# TopAndBotShieldV2-4.net
KiCad netlist of a schematic drawn in EAGLE
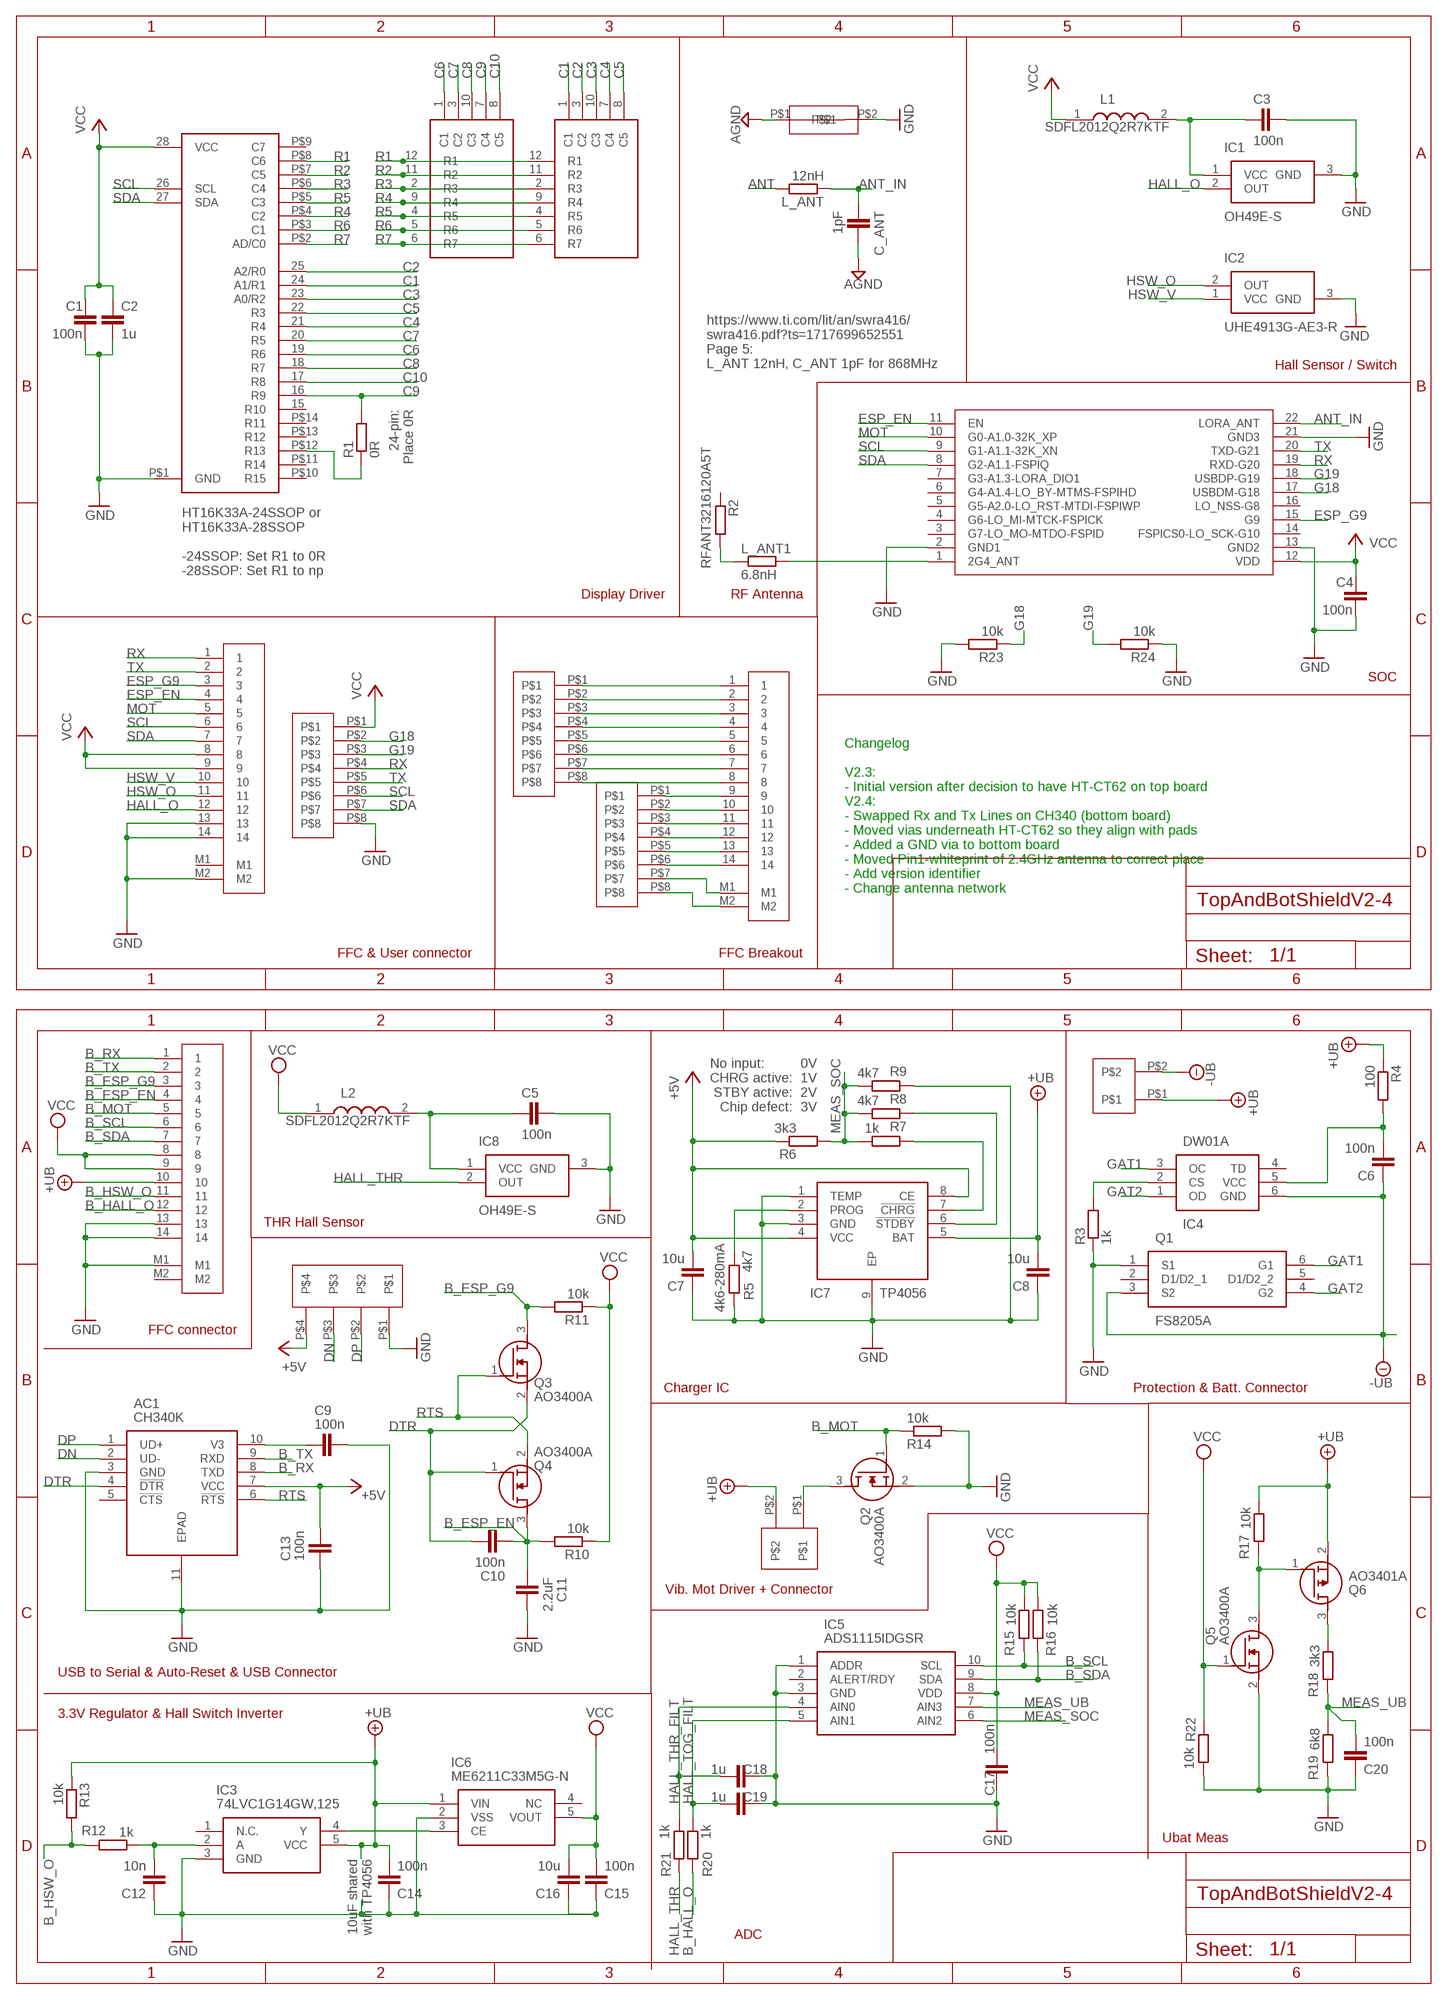
[diagram p0: schematic, sheet 1]

(export (version "E")
  (design (tool "Eeschema 10.0.6"))
  (components
    (comp (ref "AC1")
      (value "CH340K")
      (footprint "eagle-import:SOP100P600X180-11N")
      (libsource (lib "eagle-import") (part "CH340K"))
    )
    (comp (ref "C1")
      (value "100n")
      (footprint "eagle-import:C0603")
      (libsource (lib "eagle-import") (part "C-EUC0603"))
    )
    (comp (ref "C2")
      (value "1u")
      (footprint "eagle-import:C0603")
      (libsource (lib "eagle-import") (part "C-EUC0603"))
    )
    (comp (ref "C3")
      (value "100n")
      (footprint "eagle-import:C0603")
      (libsource (lib "eagle-import") (part "C-EUC0603"))
    )
    (comp (ref "C4")
      (value "100n")
      (footprint "eagle-import:C0603")
      (libsource (lib "eagle-import") (part "C-EUC0603"))
    )
    (comp (ref "C5")
      (value "100n")
      (footprint "eagle-import:C0603")
      (libsource (lib "eagle-import") (part "C-EUC0603"))
    )
    (comp (ref "C6")
      (value "100n")
      (footprint "eagle-import:C0603")
      (libsource (lib "eagle-import") (part "C-EUC0603"))
    )
    (comp (ref "C7")
      (value "10u")
      (footprint "eagle-import:C0603")
      (libsource (lib "eagle-import") (part "C-EUC0603"))
    )
    (comp (ref "C8")
      (value "10u")
      (footprint "eagle-import:C0603")
      (libsource (lib "eagle-import") (part "C-EUC0603"))
    )
    (comp (ref "C9")
      (value "100n")
      (footprint "eagle-import:C0603")
      (libsource (lib "eagle-import") (part "C-EUC0603"))
    )
    (comp (ref "C10")
      (value "100n")
      (footprint "eagle-import:C0603")
      (libsource (lib "eagle-import") (part "C-EUC0603"))
    )
    (comp (ref "C11")
      (value "2.2uF")
      (footprint "eagle-import:C0603")
      (libsource (lib "eagle-import") (part "C-EUC0603"))
    )
    (comp (ref "C12")
      (value "10n")
      (footprint "eagle-import:C0603")
      (libsource (lib "eagle-import") (part "C-EUC0603"))
    )
    (comp (ref "C13")
      (value "100n")
      (footprint "eagle-import:C0603")
      (libsource (lib "eagle-import") (part "C-EUC0603"))
    )
    (comp (ref "C14")
      (value "100n")
      (footprint "eagle-import:C0603")
      (libsource (lib "eagle-import") (part "C-EUC0603"))
    )
    (comp (ref "C15")
      (value "100n")
      (footprint "eagle-import:C0603")
      (libsource (lib "eagle-import") (part "C-EUC0603"))
    )
    (comp (ref "C16")
      (value "10u")
      (footprint "eagle-import:C0603")
      (libsource (lib "eagle-import") (part "C-EUC0603"))
    )
    (comp (ref "C17")
      (value "100n")
      (footprint "eagle-import:C0603")
      (libsource (lib "eagle-import") (part "C-EUC0603"))
    )
    (comp (ref "C18")
      (value "1u")
      (footprint "eagle-import:C0603")
      (libsource (lib "eagle-import") (part "C-EUC0603"))
    )
    (comp (ref "C19")
      (value "1u")
      (footprint "eagle-import:C0603")
      (libsource (lib "eagle-import") (part "C-EUC0603"))
    )
    (comp (ref "C20")
      (value "100n")
      (footprint "eagle-import:C0603")
      (libsource (lib "eagle-import") (part "C-EUC0603"))
    )
    (comp (ref "C_ANT")
      (value "1pF")
      (footprint "eagle-import:C0402")
      (libsource (lib "eagle-import") (part "C-EUC0402"))
    )
    (comp (ref "IC1")
      (value "OH49E-S")
      (footprint "eagle-import:SOT95P237X112-3N")
      (fields
        (field (name "ARROW_PART_NUMBER") "DRV5055A3QDBZR")
        (field (name "MOUSER_PART_NUMBER") "595-DRV5055A3QDBZR")
      )
      (libsource (lib "eagle-import") (part "DRV5055A3QDBZR"))
    )
    (comp (ref "IC2")
      (value "UHE4913G-AE3-R")
      (footprint "eagle-import:SOT95P237X112-3N")
      (fields
        (field (name "ARROW_PART_NUMBER") "DRV5055A3QDBZR")
        (field (name "MOUSER_PART_NUMBER") "595-DRV5055A3QDBZR")
      )
      (libsource (lib "eagle-import") (part "DRV5055A3QDBZR"))
    )
    (comp (ref "IC3")
      (value "74LVC1G14GW,125")
      (footprint "eagle-import:SOT65P212X110-5N")
      (fields (field (name "MOUSER_PART_NUMBER") "771-74LVC1G14GW-G"))
      (libsource (lib "eagle-import") (part "74LVC1G14GW,125"))
    )
    (comp (ref "IC4")
      (value "DW01A")
      (footprint "eagle-import:SOT95P280X135-6N")
      (fields (field (name "MANUFACTURER_PART_NUMBER") "DW01A-G"))
      (libsource (lib "eagle-import") (part "DW01A-G"))
    )
    (comp (ref "IC5")
      (value "ADS1115IDGSR")
      (footprint "eagle-import:SOP50P490X110-10N")
      (fields (field (name "MOUSER_PART_NUMBER") "595-ADS1115IDGSR"))
      (libsource (lib "eagle-import") (part "ADS1115IDGSR"))
    )
    (comp (ref "IC6")
      (value "ME6211C33M5G-N")
      (footprint "eagle-import:SOT95P282X145-5N")
      (fields (field (name "MANUFACTURER_PART_NUMBER") "ME6211C50M5G"))
      (libsource (lib "eagle-import") (part "ME6211C50M5G"))
    )
    (comp (ref "IC7")
      (value "TP4056")
      (footprint "eagle-import:SOIC127P600X175-9N")
      (fields (field (name "MANUFACTURER_PART_NUMBER") "TP4056-42-ESOP8"))
      (libsource (lib "eagle-import") (part "TP4056-42-ESOP8"))
    )
    (comp (ref "IC8")
      (value "OH49E-S")
      (footprint "eagle-import:SOT95P237X112-3N")
      (fields
        (field (name "ARROW_PART_NUMBER") "DRV5055A3QDBZR")
        (field (name "MOUSER_PART_NUMBER") "595-DRV5055A3QDBZR")
      )
      (libsource (lib "eagle-import") (part "DRV5055A3QDBZR"))
    )
    (comp (ref "L1")
      (value "SDFL2012Q2R7KTF")
      (footprint "eagle-import:INDC2112X105N")
      (libsource (lib "eagle-import") (part "SDFL2012Q2R7KTF"))
    )
    (comp (ref "L2")
      (value "SDFL2012Q2R7KTF")
      (footprint "eagle-import:INDC2112X105N")
      (libsource (lib "eagle-import") (part "SDFL2012Q2R7KTF"))
    )
    (comp (ref "L_ANT")
      (value "12nH")
      (footprint "eagle-import:R0402")
      (libsource (lib "eagle-import") (part "R-EU_R0402"))
    )
    (comp (ref "L_ANT1")
      (value "6.8nH")
      (footprint "eagle-import:R0402")
      (libsource (lib "eagle-import") (part "R-EU_R0402"))
    )
    (comp (ref "Q1")
      (value "FS8205A")
      (footprint "eagle-import:SOT95P280X125-6N")
      (libsource (lib "eagle-import") (part "FS8205A"))
    )
    (comp (ref "Q2")
      (value "AO3400A")
      (footprint "eagle-import:SOT95P280X125-3N")
      (libsource (lib "eagle-import") (part "AO3400A"))
    )
    (comp (ref "Q3")
      (value "AO3400A")
      (footprint "eagle-import:SOT95P280X125-3N")
      (libsource (lib "eagle-import") (part "AO3400A"))
    )
    (comp (ref "Q4")
      (value "AO3400A")
      (footprint "eagle-import:SOT95P280X125-3N")
      (libsource (lib "eagle-import") (part "AO3400A"))
    )
    (comp (ref "Q5")
      (value "AO3400A")
      (footprint "eagle-import:SOT95P280X125-3N")
      (libsource (lib "eagle-import") (part "AO3400A"))
    )
    (comp (ref "Q6")
      (value "AO3401A")
      (footprint "eagle-import:SOT95P280X125-3N")
      (libsource (lib "eagle-import") (part "AO3401A"))
    )
    (comp (ref "R1")
      (value "0R")
      (footprint "eagle-import:R0603")
      (libsource (lib "eagle-import") (part "R-EU_R0603"))
    )
    (comp (ref "R2")
      (value "RFANT3216120A5T")
      (footprint "eagle-import:R1206")
      (libsource (lib "eagle-import") (part "R-EU_R1206"))
    )
    (comp (ref "R3")
      (value "1k")
      (footprint "eagle-import:R0603")
      (libsource (lib "eagle-import") (part "R-EU_R0603"))
    )
    (comp (ref "R4")
      (value "100")
      (footprint "eagle-import:R0603")
      (libsource (lib "eagle-import") (part "R-EU_R0603"))
    )
    (comp (ref "R5")
      (value "4k7")
      (footprint "eagle-import:R0603")
      (libsource (lib "eagle-import") (part "R-EU_R0603"))
    )
    (comp (ref "R6")
      (value "3k3")
      (footprint "eagle-import:R0603")
      (libsource (lib "eagle-import") (part "R-EU_R0603"))
    )
    (comp (ref "R7")
      (value "1k")
      (footprint "eagle-import:R0603")
      (libsource (lib "eagle-import") (part "R-EU_R0603"))
    )
    (comp (ref "R8")
      (value "4k7")
      (footprint "eagle-import:R0603")
      (libsource (lib "eagle-import") (part "R-EU_R0603"))
    )
    (comp (ref "R9")
      (value "4k7")
      (footprint "eagle-import:R0603")
      (libsource (lib "eagle-import") (part "R-EU_R0603"))
    )
    (comp (ref "R10")
      (value "10k")
      (footprint "eagle-import:R0603")
      (libsource (lib "eagle-import") (part "R-EU_R0603"))
    )
    (comp (ref "R11")
      (value "10k")
      (footprint "eagle-import:R0603")
      (libsource (lib "eagle-import") (part "R-EU_R0603"))
    )
    (comp (ref "R12")
      (value "1k")
      (footprint "eagle-import:R0603")
      (libsource (lib "eagle-import") (part "R-EU_R0603"))
    )
    (comp (ref "R13")
      (value "10k")
      (footprint "eagle-import:R0603")
      (libsource (lib "eagle-import") (part "R-EU_R0603"))
    )
    (comp (ref "R14")
      (value "10k")
      (footprint "eagle-import:R0603")
      (libsource (lib "eagle-import") (part "R-EU_R0603"))
    )
    (comp (ref "R15")
      (value "10k")
      (footprint "eagle-import:R0603")
      (libsource (lib "eagle-import") (part "R-EU_R0603"))
    )
    (comp (ref "R16")
      (value "10k")
      (footprint "eagle-import:R0603")
      (libsource (lib "eagle-import") (part "R-EU_R0603"))
    )
    (comp (ref "R17")
      (value "10k")
      (footprint "eagle-import:R0603")
      (libsource (lib "eagle-import") (part "R-EU_R0603"))
    )
    (comp (ref "R18")
      (value "3k3")
      (footprint "eagle-import:R0603")
      (libsource (lib "eagle-import") (part "R-EU_R0603"))
    )
    (comp (ref "R19")
      (value "6k8")
      (footprint "eagle-import:R0603")
      (libsource (lib "eagle-import") (part "R-EU_R0603"))
    )
    (comp (ref "R20")
      (value "1k")
      (footprint "eagle-import:R0603")
      (libsource (lib "eagle-import") (part "R-EU_R0603"))
    )
    (comp (ref "R21")
      (value "1k")
      (footprint "eagle-import:R0603")
      (libsource (lib "eagle-import") (part "R-EU_R0603"))
    )
    (comp (ref "R22")
      (value "10k")
      (footprint "eagle-import:R0603")
      (libsource (lib "eagle-import") (part "R-EU_R0603"))
    )
    (comp (ref "R23")
      (value "10k")
      (footprint "eagle-import:R0603")
      (libsource (lib "eagle-import") (part "R-EU_R0603"))
    )
    (comp (ref "R24")
      (value "10k")
      (footprint "eagle-import:R0603")
      (libsource (lib "eagle-import") (part "R-EU_R0603"))
    )
    (comp (ref "U$1")
      (value "HT16K33A-24SSOP")
      (footprint "eagle-import:SSOP28")
      (libsource (lib "eagle-import") (part "HT16K33A"))
    )
    (comp (ref "U$2")
      (value "757A")
      (footprint "eagle-import:757A")
      (libsource (lib "eagle-import") (part "757A"))
    )
    (comp (ref "U$3")
      (value "757A")
      (footprint "eagle-import:757A")
      (libsource (lib "eagle-import") (part "757A"))
    )
    (comp (ref "U$4")
      (value "FPC-05F-14PH15")
      (footprint "eagle-import:FPC-05F-14PH15")
      (libsource (lib "eagle-import") (part "FPC-05F-14PH15"))
    )
    (comp (ref "U$5")
      (value "HT-CT62")
      (footprint "eagle-import:HT-CT62")
      (libsource (lib "eagle-import") (part "HT-CT62"))
    )
    (comp (ref "U$6")
      (value "FPC-05F-14PH15")
      (footprint "eagle-import:FPC-05F-14PH15")
      (libsource (lib "eagle-import") (part "FPC-05F-14PH15"))
    )
    (comp (ref "U$7")
      (value "NETTIE_0.6MM")
      (footprint "eagle-import:0.6MM")
      (libsource (lib "eagle-import") (part "NETTIE_0.6MM"))
    )
    (comp (ref "U$8")
      (value "8P")
      (footprint "eagle-import:8PIN")
      (libsource (lib "eagle-import") (part "8P"))
    )
    (comp (ref "U$9")
      (value "8P")
      (footprint "eagle-import:8PIN")
      (libsource (lib "eagle-import") (part "8P"))
    )
    (comp (ref "U$10")
      (value "8P")
      (footprint "eagle-import:8PIN")
      (libsource (lib "eagle-import") (part "8P"))
    )
    (comp (ref "U$11")
      (value "FPC-05F-14PH15")
      (footprint "eagle-import:FPC-05F-14PH15")
      (libsource (lib "eagle-import") (part "FPC-05F-14PH15"))
    )
    (comp (ref "U$12")
      (value "2P")
      (footprint "eagle-import:2PAD")
      (libsource (lib "eagle-import") (part "2P"))
    )
    (comp (ref "U$13")
      (value "2P")
      (footprint "eagle-import:2PAD")
      (libsource (lib "eagle-import") (part "2P"))
    )
    (comp (ref "U$14")
      (value "4P")
      (footprint "eagle-import:4PAD")
      (libsource (lib "eagle-import") (part "4P"))
    )
  )
  (nets
    (net (code "1") (name "+5V") (class "Default")
      (node (ref "AC1") (pin "7") (pinfunction "VCC_7") (pintype "power_in"))
      (node (ref "C13") (pin "1") (pinfunction "1_1") (pintype "passive"))
      (node (ref "C7") (pin "2") (pinfunction "2_2") (pintype "passive"))
      (node (ref "IC7") (pin "4") (pinfunction "VCC_4") (pintype "bidirectional"))
      (node (ref "IC7") (pin "8") (pinfunction "CE_8") (pintype "bidirectional"))
      (node (ref "R6") (pin "2") (pinfunction "2_2") (pintype "passive"))
      (node (ref "U$14") (pin "P$4") (pinfunction "P$4_P$4") (pintype "bidirectional"))
    )
    (net (code "2") (name "+UB") (class "Default")
      (node (ref "C14") (pin "2") (pinfunction "2_2") (pintype "passive"))
      (node (ref "C8") (pin "2") (pinfunction "2_2") (pintype "passive"))
      (node (ref "IC3") (pin "5") (pinfunction "VCC_5") (pintype "bidirectional"))
      (node (ref "IC6") (pin "1") (pinfunction "VIN_1") (pintype "bidirectional"))
      (node (ref "IC7") (pin "5") (pinfunction "BAT_5") (pintype "bidirectional"))
      (node (ref "Q6") (pin "2") (pinfunction "S_2") (pintype "bidirectional"))
      (node (ref "R13") (pin "1") (pinfunction "1_1") (pintype "passive"))
      (node (ref "R17") (pin "1") (pinfunction "1_1") (pintype "passive"))
      (node (ref "R4") (pin "1") (pinfunction "1_1") (pintype "passive"))
      (node (ref "U$11") (pin "10") (pinfunction "10_10") (pintype "bidirectional"))
      (node (ref "U$12") (pin "P$1") (pinfunction "P$1_P$1") (pintype "bidirectional"))
      (node (ref "U$13") (pin "P$2") (pinfunction "P$2_P$2") (pintype "bidirectional"))
    )
    (net (code "3") (name "-UB") (class "Default")
      (node (ref "C6") (pin "1") (pinfunction "1_1") (pintype "passive"))
      (node (ref "IC4") (pin "6") (pinfunction "GND_6") (pintype "bidirectional"))
      (node (ref "Q1") (pin "3") (pinfunction "S2_3") (pintype "bidirectional"))
      (node (ref "U$12") (pin "P$2") (pinfunction "P$2_P$2") (pintype "bidirectional"))
    )
    (net (code "4") (name "/ANT") (class "Default")
      (node (ref "L_ANT") (pin "2") (pinfunction "2_2") (pintype "passive"))
    )
    (net (code "5") (name "/ANT_IN") (class "Default")
      (node (ref "C_ANT") (pin "1") (pinfunction "1_1") (pintype "passive"))
      (node (ref "L_ANT") (pin "1") (pinfunction "1_1") (pintype "passive"))
      (node (ref "U$5") (pin "22") (pinfunction "LORA_ANT_22") (pintype "bidirectional"))
    )
    (net (code "6") (name "/B_ESP_EN") (class "Default")
      (node (ref "C10") (pin "2") (pinfunction "2_2") (pintype "passive"))
      (node (ref "C11") (pin "2") (pinfunction "2_2") (pintype "passive"))
      (node (ref "Q4") (pin "3") (pinfunction "D_3") (pintype "bidirectional"))
      (node (ref "R10") (pin "2") (pinfunction "2_2") (pintype "passive"))
      (node (ref "U$11") (pin "4") (pinfunction "4_4") (pintype "bidirectional"))
    )
    (net (code "7") (name "/B_ESP_G9") (class "Default")
      (node (ref "Q3") (pin "3") (pinfunction "D_3") (pintype "bidirectional"))
      (node (ref "R11") (pin "2") (pinfunction "2_2") (pintype "passive"))
      (node (ref "U$11") (pin "3") (pinfunction "3_3") (pintype "bidirectional"))
    )
    (net (code "8") (name "/B_HALL_O") (class "Default")
      (node (ref "R20") (pin "2") (pinfunction "2_2") (pintype "passive"))
      (node (ref "U$11") (pin "12") (pinfunction "12_12") (pintype "bidirectional"))
    )
    (net (code "9") (name "/B_HSW_O") (class "Default")
      (node (ref "R12") (pin "2") (pinfunction "2_2") (pintype "passive"))
      (node (ref "R13") (pin "2") (pinfunction "2_2") (pintype "passive"))
      (node (ref "U$11") (pin "11") (pinfunction "11_11") (pintype "bidirectional"))
    )
    (net (code "10") (name "/B_MOT") (class "Default")
      (node (ref "Q2") (pin "1") (pinfunction "G_1") (pintype "bidirectional"))
      (node (ref "R14") (pin "1") (pinfunction "1_1") (pintype "passive"))
      (node (ref "U$11") (pin "5") (pinfunction "5_5") (pintype "bidirectional"))
    )
    (net (code "11") (name "/B_RX") (class "Default")
      (node (ref "AC1") (pin "8") (pinfunction "TXD_8") (pintype "bidirectional"))
      (node (ref "U$11") (pin "1") (pinfunction "1_1") (pintype "bidirectional"))
    )
    (net (code "12") (name "/B_SCL") (class "Default")
      (node (ref "IC5") (pin "10") (pinfunction "SCL_10") (pintype "bidirectional"))
      (node (ref "R15") (pin "2") (pinfunction "2_2") (pintype "passive"))
      (node (ref "U$11") (pin "6") (pinfunction "6_6") (pintype "bidirectional"))
    )
    (net (code "13") (name "/B_SDA") (class "Default")
      (node (ref "IC5") (pin "9") (pinfunction "SDA_9") (pintype "bidirectional"))
      (node (ref "R16") (pin "2") (pinfunction "2_2") (pintype "passive"))
      (node (ref "U$11") (pin "7") (pinfunction "7_7") (pintype "bidirectional"))
    )
    (net (code "14") (name "/B_TX") (class "Default")
      (node (ref "AC1") (pin "9") (pinfunction "RXD_9") (pintype "bidirectional"))
      (node (ref "U$11") (pin "2") (pinfunction "2_2") (pintype "bidirectional"))
    )
    (net (code "15") (name "/C1") (class "Default")
      (node (ref "U$1") (pin "24") (pinfunction "A1/R1_24") (pintype "bidirectional"))
      (node (ref "U$3") (pin "1") (pinfunction "C1_1") (pintype "bidirectional"))
    )
    (net (code "16") (name "/C2") (class "Default")
      (node (ref "U$1") (pin "25") (pinfunction "A2/R0_25") (pintype "bidirectional"))
      (node (ref "U$3") (pin "3") (pinfunction "C2_3") (pintype "bidirectional"))
    )
    (net (code "17") (name "/C3") (class "Default")
      (node (ref "U$1") (pin "23") (pinfunction "A0/R2_23") (pintype "bidirectional"))
      (node (ref "U$3") (pin "10") (pinfunction "C3_10") (pintype "bidirectional"))
    )
    (net (code "18") (name "/C4") (class "Default")
      (node (ref "U$1") (pin "21") (pinfunction "R4_21") (pintype "bidirectional"))
      (node (ref "U$3") (pin "7") (pinfunction "C4_7") (pintype "bidirectional"))
    )
    (net (code "19") (name "/C5") (class "Default")
      (node (ref "U$1") (pin "22") (pinfunction "R3_22") (pintype "bidirectional"))
      (node (ref "U$3") (pin "8") (pinfunction "C5_8") (pintype "bidirectional"))
    )
    (net (code "20") (name "/C6") (class "Default")
      (node (ref "U$1") (pin "19") (pinfunction "R6_19") (pintype "bidirectional"))
      (node (ref "U$2") (pin "1") (pinfunction "C1_1") (pintype "bidirectional"))
    )
    (net (code "21") (name "/C7") (class "Default")
      (node (ref "U$1") (pin "20") (pinfunction "R5_20") (pintype "bidirectional"))
      (node (ref "U$2") (pin "3") (pinfunction "C2_3") (pintype "bidirectional"))
    )
    (net (code "22") (name "/C8") (class "Default")
      (node (ref "U$1") (pin "18") (pinfunction "R7_18") (pintype "bidirectional"))
      (node (ref "U$2") (pin "10") (pinfunction "C3_10") (pintype "bidirectional"))
    )
    (net (code "23") (name "/C9") (class "Default")
      (node (ref "R1") (pin "2") (pinfunction "2_2") (pintype "passive"))
      (node (ref "U$1") (pin "16") (pinfunction "R9_16") (pintype "bidirectional"))
      (node (ref "U$2") (pin "7") (pinfunction "C4_7") (pintype "bidirectional"))
    )
    (net (code "24") (name "/C10") (class "Default")
      (node (ref "U$1") (pin "17") (pinfunction "R8_17") (pintype "bidirectional"))
      (node (ref "U$2") (pin "8") (pinfunction "C5_8") (pintype "bidirectional"))
    )
    (net (code "25") (name "/DN") (class "Default")
      (node (ref "AC1") (pin "2") (pinfunction "UD-_2") (pintype "bidirectional"))
      (node (ref "U$14") (pin "P$3") (pinfunction "P$3_P$3") (pintype "bidirectional"))
    )
    (net (code "26") (name "/DP") (class "Default")
      (node (ref "AC1") (pin "1") (pinfunction "UD+_1") (pintype "bidirectional"))
      (node (ref "U$14") (pin "P$2") (pinfunction "P$2_P$2") (pintype "bidirectional"))
    )
    (net (code "27") (name "/DTR") (class "Default")
      (node (ref "AC1") (pin "4") (pinfunction "~{DTR}_4") (pintype "bidirectional"))
      (node (ref "C10") (pin "1") (pinfunction "1_1") (pintype "passive"))
      (node (ref "Q3") (pin "2") (pinfunction "S_2") (pintype "bidirectional"))
      (node (ref "Q4") (pin "1") (pinfunction "G_1") (pintype "bidirectional"))
    )
    (net (code "28") (name "/ESP_EN") (class "Default")
      (node (ref "U$5") (pin "11") (pinfunction "EN_11") (pintype "bidirectional"))
      (node (ref "U$6") (pin "4") (pinfunction "4_4") (pintype "bidirectional"))
    )
    (net (code "29") (name "/ESP_G9") (class "Default")
      (node (ref "U$5") (pin "15") (pinfunction "G9_15") (pintype "bidirectional"))
      (node (ref "U$6") (pin "3") (pinfunction "3_3") (pintype "bidirectional"))
    )
    (net (code "30") (name "/G18") (class "Default")
      (node (ref "R23") (pin "1") (pinfunction "1_1") (pintype "passive"))
      (node (ref "U$5") (pin "17") (pinfunction "USBDM-G18_17") (pintype "bidirectional"))
      (node (ref "U$8") (pin "P$2") (pinfunction "P$2_P$2") (pintype "bidirectional"))
    )
    (net (code "31") (name "/G19") (class "Default")
      (node (ref "R24") (pin "2") (pinfunction "2_2") (pintype "passive"))
      (node (ref "U$5") (pin "18") (pinfunction "USBDP-G19_18") (pintype "bidirectional"))
      (node (ref "U$8") (pin "P$3") (pinfunction "P$3_P$3") (pintype "bidirectional"))
    )
    (net (code "32") (name "/GAT1") (class "Default")
      (node (ref "IC4") (pin "3") (pinfunction "OC_3") (pintype "bidirectional"))
      (node (ref "Q1") (pin "6") (pinfunction "G1_6") (pintype "bidirectional"))
    )
    (net (code "33") (name "/GAT2") (class "Default")
      (node (ref "IC4") (pin "1") (pinfunction "OD_1") (pintype "bidirectional"))
      (node (ref "Q1") (pin "4") (pinfunction "G2_4") (pintype "bidirectional"))
    )
    (net (code "34") (name "/HALL_O") (class "Default")
      (node (ref "IC1") (pin "2") (pinfunction "OUT_2") (pintype "bidirectional"))
      (node (ref "U$6") (pin "12") (pinfunction "12_12") (pintype "bidirectional"))
    )
    (net (code "35") (name "/HALL_THR") (class "Default")
      (node (ref "IC8") (pin "2") (pinfunction "OUT_2") (pintype "bidirectional"))
      (node (ref "R21") (pin "2") (pinfunction "2_2") (pintype "passive"))
    )
    (net (code "36") (name "/HALL_THR_FILT") (class "Default")
      (node (ref "C18") (pin "1") (pinfunction "1_1") (pintype "passive"))
      (node (ref "IC5") (pin "4") (pinfunction "AIN0_4") (pintype "bidirectional"))
      (node (ref "R21") (pin "1") (pinfunction "1_1") (pintype "passive"))
    )
    (net (code "37") (name "/HALL_TOG_FILT") (class "Default")
      (node (ref "C19") (pin "1") (pinfunction "1_1") (pintype "passive"))
      (node (ref "IC5") (pin "5") (pinfunction "AIN1_5") (pintype "bidirectional"))
      (node (ref "R20") (pin "1") (pinfunction "1_1") (pintype "passive"))
    )
    (net (code "38") (name "/HSW_O") (class "Default")
      (node (ref "IC2") (pin "2") (pinfunction "OUT_2") (pintype "bidirectional"))
      (node (ref "U$6") (pin "11") (pinfunction "11_11") (pintype "bidirectional"))
    )
    (net (code "39") (name "/HSW_V") (class "Default")
      (node (ref "IC2") (pin "1") (pinfunction "VCC_1") (pintype "bidirectional"))
      (node (ref "U$6") (pin "10") (pinfunction "10_10") (pintype "bidirectional"))
    )
    (net (code "40") (name "/MEAS_SOC") (class "Default")
      (node (ref "IC5") (pin "6") (pinfunction "AIN2_6") (pintype "bidirectional"))
      (node (ref "R6") (pin "1") (pinfunction "1_1") (pintype "passive"))
      (node (ref "R7") (pin "2") (pinfunction "2_2") (pintype "passive"))
      (node (ref "R8") (pin "2") (pinfunction "2_2") (pintype "passive"))
      (node (ref "R9") (pin "2") (pinfunction "2_2") (pintype "passive"))
    )
    (net (code "41") (name "/MEAS_UB") (class "Default")
      (node (ref "C20") (pin "2") (pinfunction "2_2") (pintype "passive"))
      (node (ref "IC5") (pin "7") (pinfunction "AIN3_7") (pintype "bidirectional"))
      (node (ref "R18") (pin "2") (pinfunction "2_2") (pintype "passive"))
      (node (ref "R19") (pin "1") (pinfunction "1_1") (pintype "passive"))
    )
    (net (code "42") (name "/MOT") (class "Default")
      (node (ref "U$5") (pin "10") (pinfunction "G0-A1.0-32K_XP_10") (pintype "bidirectional"))
      (node (ref "U$6") (pin "5") (pinfunction "5_5") (pintype "bidirectional"))
    )
    (net (code "43") (name "/R1") (class "Default")
      (node (ref "U$1") (pin "P$8") (pinfunction "C6_P$8") (pintype "bidirectional"))
      (node (ref "U$2") (pin "12") (pinfunction "R1_12") (pintype "bidirectional"))
      (node (ref "U$3") (pin "12") (pinfunction "R1_12") (pintype "bidirectional"))
    )
    (net (code "44") (name "/R2") (class "Default")
      (node (ref "U$1") (pin "P$7") (pinfunction "C5_P$7") (pintype "bidirectional"))
      (node (ref "U$2") (pin "11") (pinfunction "R2_11") (pintype "bidirectional"))
      (node (ref "U$3") (pin "11") (pinfunction "R2_11") (pintype "bidirectional"))
    )
    (net (code "45") (name "/R3") (class "Default")
      (node (ref "U$1") (pin "P$6") (pinfunction "C4_P$6") (pintype "bidirectional"))
      (node (ref "U$2") (pin "2") (pinfunction "R3_2") (pintype "bidirectional"))
      (node (ref "U$3") (pin "2") (pinfunction "R3_2") (pintype "bidirectional"))
    )
    (net (code "46") (name "/R4") (class "Default")
      (node (ref "U$1") (pin "P$4") (pinfunction "C2_P$4") (pintype "bidirectional"))
      (node (ref "U$2") (pin "9") (pinfunction "R4_9") (pintype "bidirectional"))
      (node (ref "U$3") (pin "9") (pinfunction "R4_9") (pintype "bidirectional"))
    )
    (net (code "47") (name "/R5") (class "Default")
      (node (ref "U$1") (pin "P$5") (pinfunction "C3_P$5") (pintype "bidirectional"))
      (node (ref "U$2") (pin "4") (pinfunction "R5_4") (pintype "bidirectional"))
      (node (ref "U$3") (pin "4") (pinfunction "R5_4") (pintype "bidirectional"))
    )
    (net (code "48") (name "/R6") (class "Default")
      (node (ref "U$1") (pin "P$3") (pinfunction "C1_P$3") (pintype "bidirectional"))
      (node (ref "U$2") (pin "5") (pinfunction "R6_5") (pintype "bidirectional"))
      (node (ref "U$3") (pin "5") (pinfunction "R6_5") (pintype "bidirectional"))
    )
    (net (code "49") (name "/R7") (class "Default")
      (node (ref "U$1") (pin "P$2") (pinfunction "AD/C0_P$2") (pintype "bidirectional"))
      (node (ref "U$2") (pin "6") (pinfunction "R7_6") (pintype "bidirectional"))
      (node (ref "U$3") (pin "6") (pinfunction "R7_6") (pintype "bidirectional"))
    )
    (net (code "50") (name "/RTS") (class "Default")
      (node (ref "AC1") (pin "6") (pinfunction "~{RTS}_6") (pintype "bidirectional"))
      (node (ref "Q3") (pin "1") (pinfunction "G_1") (pintype "bidirectional"))
      (node (ref "Q4") (pin "2") (pinfunction "S_2") (pintype "bidirectional"))
    )
    (net (code "51") (name "/RX") (class "Default")
      (node (ref "U$5") (pin "19") (pinfunction "RXD-G20_19") (pintype "bidirectional"))
      (node (ref "U$6") (pin "1") (pinfunction "1_1") (pintype "bidirectional"))
      (node (ref "U$8") (pin "P$4") (pinfunction "P$4_P$4") (pintype "bidirectional"))
    )
    (net (code "52") (name "/SCL") (class "Default")
      (node (ref "U$1") (pin "26") (pinfunction "SCL_26") (pintype "bidirectional"))
      (node (ref "U$5") (pin "9") (pinfunction "G1-A1.1-32K_XN_9") (pintype "bidirectional"))
      (node (ref "U$6") (pin "6") (pinfunction "6_6") (pintype "bidirectional"))
      (node (ref "U$8") (pin "P$6") (pinfunction "P$6_P$6") (pintype "bidirectional"))
    )
    (net (code "53") (name "/SDA") (class "Default")
      (node (ref "U$1") (pin "27") (pinfunction "SDA_27") (pintype "bidirectional"))
      (node (ref "U$5") (pin "8") (pinfunction "G2-A1.1-FSPIQ_8") (pintype "bidirectional"))
      (node (ref "U$6") (pin "7") (pinfunction "7_7") (pintype "bidirectional"))
      (node (ref "U$8") (pin "P$7") (pinfunction "P$7_P$7") (pintype "bidirectional"))
    )
    (net (code "54") (name "/TX") (class "Default")
      (node (ref "U$5") (pin "20") (pinfunction "TXD-G21_20") (pintype "bidirectional"))
      (node (ref "U$6") (pin "2") (pinfunction "2_2") (pintype "bidirectional"))
      (node (ref "U$8") (pin "P$5") (pinfunction "P$5_P$5") (pintype "bidirectional"))
    )
    (net (code "55") (name "AGND") (class "Default")
      (node (ref "C_ANT") (pin "2") (pinfunction "2_2") (pintype "passive"))
      (node (ref "U$7") (pin "P$1") (pinfunction "P$1_P$1") (pintype "bidirectional"))
    )
    (net (code "56") (name "GND") (class "Default")
      (node (ref "AC1") (pin "11") (pinfunction "EPAD_11") (pintype "power_in"))
      (node (ref "AC1") (pin "3") (pinfunction "GND_3") (pintype "power_in"))
      (node (ref "C1") (pin "2") (pinfunction "2_2") (pintype "passive"))
      (node (ref "C11") (pin "1") (pinfunction "1_1") (pintype "passive"))
      (node (ref "C12") (pin "1") (pinfunction "1_1") (pintype "passive"))
      (node (ref "C13") (pin "2") (pinfunction "2_2") (pintype "passive"))
      (node (ref "C14") (pin "1") (pinfunction "1_1") (pintype "passive"))
      (node (ref "C15") (pin "1") (pinfunction "1_1") (pintype "passive"))
      (node (ref "C16") (pin "1") (pinfunction "1_1") (pintype "passive"))
      (node (ref "C17") (pin "2") (pinfunction "2_2") (pintype "passive"))
      (node (ref "C18") (pin "2") (pinfunction "2_2") (pintype "passive"))
      (node (ref "C19") (pin "2") (pinfunction "2_2") (pintype "passive"))
      (node (ref "C2") (pin "2") (pinfunction "2_2") (pintype "passive"))
      (node (ref "C20") (pin "1") (pinfunction "1_1") (pintype "passive"))
      (node (ref "C3") (pin "1") (pinfunction "1_1") (pintype "passive"))
      (node (ref "C4") (pin "2") (pinfunction "2_2") (pintype "passive"))
      (node (ref "C5") (pin "1") (pinfunction "1_1") (pintype "passive"))
      (node (ref "C7") (pin "1") (pinfunction "1_1") (pintype "passive"))
      (node (ref "C8") (pin "1") (pinfunction "1_1") (pintype "passive"))
      (node (ref "C9") (pin "1") (pinfunction "1_1") (pintype "passive"))
      (node (ref "IC1") (pin "3") (pinfunction "GND_3") (pintype "bidirectional"))
      (node (ref "IC2") (pin "3") (pinfunction "GND_3") (pintype "bidirectional"))
      (node (ref "IC3") (pin "3") (pinfunction "GND_3") (pintype "bidirectional"))
      (node (ref "IC5") (pin "1") (pinfunction "ADDR_1") (pintype "bidirectional"))
      (node (ref "IC5") (pin "3") (pinfunction "GND_3") (pintype "bidirectional"))
      (node (ref "IC6") (pin "2") (pinfunction "VSS_2") (pintype "bidirectional"))
      (node (ref "IC7") (pin "1") (pinfunction "TEMP_1") (pintype "bidirectional"))
      (node (ref "IC7") (pin "3") (pinfunction "GND_3") (pintype "bidirectional"))
      (node (ref "IC7") (pin "9") (pinfunction "EP_9") (pintype "bidirectional"))
      (node (ref "IC8") (pin "3") (pinfunction "GND_3") (pintype "bidirectional"))
      (node (ref "Q1") (pin "1") (pinfunction "S1_1") (pintype "bidirectional"))
      (node (ref "Q2") (pin "2") (pinfunction "S_2") (pintype "bidirectional"))
      (node (ref "Q5") (pin "2") (pinfunction "S_2") (pintype "bidirectional"))
      (node (ref "R14") (pin "2") (pinfunction "2_2") (pintype "passive"))
      (node (ref "R19") (pin "2") (pinfunction "2_2") (pintype "passive"))
      (node (ref "R22") (pin "1") (pinfunction "1_1") (pintype "passive"))
      (node (ref "R23") (pin "2") (pinfunction "2_2") (pintype "passive"))
      (node (ref "R24") (pin "1") (pinfunction "1_1") (pintype "passive"))
      (node (ref "R3") (pin "1") (pinfunction "1_1") (pintype "passive"))
      (node (ref "R5") (pin "1") (pinfunction "1_1") (pintype "passive"))
      (node (ref "R9") (pin "1") (pinfunction "1_1") (pintype "passive"))
      (node (ref "U$1") (pin "P$1") (pinfunction "GND_P$1") (pintype "power_in"))
      (node (ref "U$11") (pin "13") (pinfunction "13_13") (pintype "bidirectional"))
      (node (ref "U$11") (pin "14") (pinfunction "14_14") (pintype "bidirectional"))
      (node (ref "U$11") (pin "M1") (pinfunction "M1_M1") (pintype "bidirectional"))
      (node (ref "U$14") (pin "P$1") (pinfunction "P$1_P$1") (pintype "bidirectional"))
      (node (ref "U$5") (pin "13") (pinfunction "GND2_13") (pintype "bidirectional"))
      (node (ref "U$5") (pin "2") (pinfunction "GND1_2") (pintype "bidirectional"))
      (node (ref "U$5") (pin "21") (pinfunction "GND3_21") (pintype "bidirectional"))
      (node (ref "U$6") (pin "13") (pinfunction "13_13") (pintype "bidirectional"))
      (node (ref "U$6") (pin "14") (pinfunction "14_14") (pintype "bidirectional"))
      (node (ref "U$6") (pin "M2") (pinfunction "M2_M2") (pintype "bidirectional"))
      (node (ref "U$7") (pin "P$2") (pinfunction "P$2_P$2") (pintype "bidirectional"))
      (node (ref "U$8") (pin "P$8") (pinfunction "P$8_P$8") (pintype "bidirectional"))
    )
    (net (code "57") (name "Net-(AC1-V3)") (class "Default")
      (node (ref "AC1") (pin "10") (pinfunction "V3_10") (pintype "power_in"))
      (node (ref "C9") (pin "2") (pinfunction "2_2") (pintype "passive"))
    )
    (net (code "58") (name "Net-(IC1-VCC)") (class "Default")
      (node (ref "C3") (pin "2") (pinfunction "2_2") (pintype "passive"))
      (node (ref "IC1") (pin "1") (pinfunction "VCC_1") (pintype "bidirectional"))
      (node (ref "L1") (pin "2") (pinfunction "2_2") (pintype "bidirectional"))
    )
    (net (code "59") (name "Net-(IC3-A)") (class "Default")
      (node (ref "C12") (pin "2") (pinfunction "2_2") (pintype "passive"))
      (node (ref "IC3") (pin "2") (pinfunction "A_2") (pintype "bidirectional"))
      (node (ref "R12") (pin "1") (pinfunction "1_1") (pintype "passive"))
    )
    (net (code "60") (name "Net-(IC3-Y)") (class "Default")
      (node (ref "IC3") (pin "4") (pinfunction "Y_4") (pintype "bidirectional"))
      (node (ref "IC6") (pin "3") (pinfunction "CE_3") (pintype "bidirectional"))
    )
    (net (code "61") (name "Net-(IC4-CS)") (class "Default")
      (node (ref "IC4") (pin "2") (pinfunction "CS_2") (pintype "bidirectional"))
      (node (ref "R3") (pin "2") (pinfunction "2_2") (pintype "passive"))
    )
    (net (code "62") (name "Net-(IC4-VCC)") (class "Default")
      (node (ref "C6") (pin "2") (pinfunction "2_2") (pintype "passive"))
      (node (ref "IC4") (pin "5") (pinfunction "VCC_5") (pintype "bidirectional"))
      (node (ref "R4") (pin "2") (pinfunction "2_2") (pintype "passive"))
    )
    (net (code "63") (name "Net-(IC7-PROG)") (class "Default")
      (node (ref "IC7") (pin "2") (pinfunction "PROG_2") (pintype "bidirectional"))
      (node (ref "R5") (pin "2") (pinfunction "2_2") (pintype "passive"))
    )
    (net (code "64") (name "Net-(IC7-~{CHRG})") (class "Default")
      (node (ref "IC7") (pin "7") (pinfunction "~{CHRG}_7") (pintype "bidirectional"))
      (node (ref "R7") (pin "1") (pinfunction "1_1") (pintype "passive"))
    )
    (net (code "65") (name "Net-(IC7-~{STDBY})") (class "Default")
      (node (ref "IC7") (pin "6") (pinfunction "~{STDBY}_6") (pintype "bidirectional"))
      (node (ref "R8") (pin "1") (pinfunction "1_1") (pintype "passive"))
    )
    (net (code "66") (name "Net-(IC8-VCC)") (class "Default")
      (node (ref "C5") (pin "2") (pinfunction "2_2") (pintype "passive"))
      (node (ref "IC8") (pin "1") (pinfunction "VCC_1") (pintype "bidirectional"))
      (node (ref "L2") (pin "2") (pinfunction "2_2") (pintype "bidirectional"))
    )
    (net (code "67") (name "Net-(L_ANT1-Pad2)") (class "Default")
      (node (ref "L_ANT1") (pin "2") (pinfunction "2_2") (pintype "passive"))
      (node (ref "R2") (pin "2") (pinfunction "2_2") (pintype "passive"))
    )
    (net (code "68") (name "Net-(Q2-D)") (class "Default")
      (node (ref "Q2") (pin "3") (pinfunction "D_3") (pintype "bidirectional"))
      (node (ref "U$13") (pin "P$1") (pinfunction "P$1_P$1") (pintype "bidirectional"))
    )
    (net (code "69") (name "Net-(Q5-D)") (class "Default")
      (node (ref "Q5") (pin "3") (pinfunction "D_3") (pintype "bidirectional"))
      (node (ref "Q6") (pin "1") (pinfunction "G_1") (pintype "bidirectional"))
      (node (ref "R17") (pin "2") (pinfunction "2_2") (pintype "passive"))
    )
    (net (code "70") (name "Net-(Q6-D)") (class "Default")
      (node (ref "Q6") (pin "3") (pinfunction "D_3") (pintype "bidirectional"))
      (node (ref "R18") (pin "1") (pinfunction "1_1") (pintype "passive"))
    )
    (net (code "71") (name "Net-(U$1-R13)") (class "Default")
      (node (ref "R1") (pin "1") (pinfunction "1_1") (pintype "passive"))
      (node (ref "U$1") (pin "P$12") (pinfunction "R13_P$12") (pintype "bidirectional"))
    )
    (net (code "72") (name "Net-(U$4-Pad1)") (class "Default")
      (node (ref "U$4") (pin "1") (pinfunction "1_1") (pintype "bidirectional"))
      (node (ref "U$9") (pin "P$1") (pinfunction "P$1_P$1") (pintype "bidirectional"))
    )
    (net (code "73") (name "Net-(U$4-Pad2)") (class "Default")
      (node (ref "U$4") (pin "2") (pinfunction "2_2") (pintype "bidirectional"))
      (node (ref "U$9") (pin "P$2") (pinfunction "P$2_P$2") (pintype "bidirectional"))
    )
    (net (code "74") (name "Net-(U$4-Pad3)") (class "Default")
      (node (ref "U$4") (pin "3") (pinfunction "3_3") (pintype "bidirectional"))
      (node (ref "U$9") (pin "P$3") (pinfunction "P$3_P$3") (pintype "bidirectional"))
    )
    (net (code "75") (name "Net-(U$4-Pad4)") (class "Default")
      (node (ref "U$4") (pin "4") (pinfunction "4_4") (pintype "bidirectional"))
      (node (ref "U$9") (pin "P$4") (pinfunction "P$4_P$4") (pintype "bidirectional"))
    )
    (net (code "76") (name "Net-(U$4-Pad5)") (class "Default")
      (node (ref "U$4") (pin "5") (pinfunction "5_5") (pintype "bidirectional"))
      (node (ref "U$9") (pin "P$5") (pinfunction "P$5_P$5") (pintype "bidirectional"))
    )
    (net (code "77") (name "Net-(U$4-Pad6)") (class "Default")
      (node (ref "U$4") (pin "6") (pinfunction "6_6") (pintype "bidirectional"))
      (node (ref "U$9") (pin "P$6") (pinfunction "P$6_P$6") (pintype "bidirectional"))
    )
    (net (code "78") (name "Net-(U$4-Pad7)") (class "Default")
      (node (ref "U$4") (pin "7") (pinfunction "7_7") (pintype "bidirectional"))
      (node (ref "U$9") (pin "P$7") (pinfunction "P$7_P$7") (pintype "bidirectional"))
    )
    (net (code "79") (name "Net-(U$4-Pad8)") (class "Default")
      (node (ref "U$4") (pin "8") (pinfunction "8_8") (pintype "bidirectional"))
      (node (ref "U$9") (pin "P$8") (pinfunction "P$8_P$8") (pintype "bidirectional"))
    )
    (net (code "80") (name "Net-(U$5-2G4_ANT)") (class "Default")
      (node (ref "L_ANT1") (pin "1") (pinfunction "1_1") (pintype "passive"))
      (node (ref "U$5") (pin "1") (pinfunction "2G4_ANT_1") (pintype "bidirectional"))
    )
    (net (code "81") (name "Net-(U$10-PadP$1)") (class "Default")
      (node (ref "U$10") (pin "P$1") (pinfunction "P$1_P$1") (pintype "bidirectional"))
      (node (ref "U$4") (pin "9") (pinfunction "9_9") (pintype "bidirectional"))
    )
    (net (code "82") (name "Net-(U$10-PadP$2)") (class "Default")
      (node (ref "U$10") (pin "P$2") (pinfunction "P$2_P$2") (pintype "bidirectional"))
      (node (ref "U$4") (pin "10") (pinfunction "10_10") (pintype "bidirectional"))
    )
    (net (code "83") (name "Net-(U$10-PadP$3)") (class "Default")
      (node (ref "U$10") (pin "P$3") (pinfunction "P$3_P$3") (pintype "bidirectional"))
      (node (ref "U$4") (pin "11") (pinfunction "11_11") (pintype "bidirectional"))
    )
    (net (code "84") (name "Net-(U$10-PadP$4)") (class "Default")
      (node (ref "U$10") (pin "P$4") (pinfunction "P$4_P$4") (pintype "bidirectional"))
      (node (ref "U$4") (pin "12") (pinfunction "12_12") (pintype "bidirectional"))
    )
    (net (code "85") (name "Net-(U$10-PadP$5)") (class "Default")
      (node (ref "U$10") (pin "P$5") (pinfunction "P$5_P$5") (pintype "bidirectional"))
      (node (ref "U$4") (pin "13") (pinfunction "13_13") (pintype "bidirectional"))
    )
    (net (code "86") (name "Net-(U$10-PadP$6)") (class "Default")
      (node (ref "U$10") (pin "P$6") (pinfunction "P$6_P$6") (pintype "bidirectional"))
      (node (ref "U$4") (pin "14") (pinfunction "14_14") (pintype "bidirectional"))
    )
    (net (code "87") (name "Net-(U$10-PadP$7)") (class "Default")
      (node (ref "U$10") (pin "P$7") (pinfunction "P$7_P$7") (pintype "bidirectional"))
      (node (ref "U$4") (pin "M1") (pinfunction "M1_M1") (pintype "bidirectional"))
    )
    (net (code "88") (name "Net-(U$10-PadP$8)") (class "Default")
      (node (ref "U$10") (pin "P$8") (pinfunction "P$8_P$8") (pintype "bidirectional"))
      (node (ref "U$4") (pin "M2") (pinfunction "M2_M2") (pintype "bidirectional"))
    )
    (net (code "89") (name "VCC") (class "Default")
      (node (ref "C1") (pin "1") (pinfunction "1_1") (pintype "passive"))
      (node (ref "C15") (pin "2") (pinfunction "2_2") (pintype "passive"))
      (node (ref "C16") (pin "2") (pinfunction "2_2") (pintype "passive"))
      (node (ref "C17") (pin "1") (pinfunction "1_1") (pintype "passive"))
      (node (ref "C2") (pin "1") (pinfunction "1_1") (pintype "passive"))
      (node (ref "C4") (pin "1") (pinfunction "1_1") (pintype "passive"))
      (node (ref "IC5") (pin "8") (pinfunction "VDD_8") (pintype "bidirectional"))
      (node (ref "IC6") (pin "5") (pinfunction "VOUT_5") (pintype "bidirectional"))
      (node (ref "L1") (pin "1") (pinfunction "1_1") (pintype "bidirectional"))
      (node (ref "L2") (pin "1") (pinfunction "1_1") (pintype "bidirectional"))
      (node (ref "Q5") (pin "1") (pinfunction "G_1") (pintype "bidirectional"))
      (node (ref "R10") (pin "1") (pinfunction "1_1") (pintype "passive"))
      (node (ref "R11") (pin "1") (pinfunction "1_1") (pintype "passive"))
      (node (ref "R15") (pin "1") (pinfunction "1_1") (pintype "passive"))
      (node (ref "R16") (pin "1") (pinfunction "1_1") (pintype "passive"))
      (node (ref "R22") (pin "2") (pinfunction "2_2") (pintype "passive"))
      (node (ref "U$1") (pin "28") (pinfunction "VCC_28") (pintype "power_in"))
      (node (ref "U$11") (pin "8") (pinfunction "8_8") (pintype "bidirectional"))
      (node (ref "U$11") (pin "9") (pinfunction "9_9") (pintype "bidirectional"))
      (node (ref "U$5") (pin "12") (pinfunction "VDD_12") (pintype "bidirectional"))
      (node (ref "U$6") (pin "8") (pinfunction "8_8") (pintype "bidirectional"))
      (node (ref "U$6") (pin "9") (pinfunction "9_9") (pintype "bidirectional"))
      (node (ref "U$8") (pin "P$1") (pinfunction "P$1_P$1") (pintype "bidirectional"))
    )
    (net (code "90") (name "unconnected-(AC1-~{CTS}-Pad5)") (class "Default")
      (node (ref "AC1") (pin "5") (pinfunction "~{CTS}_5") (pintype "bidirectional"))
    )
    (net (code "91") (name "unconnected-(IC3-N.C.-Pad1)") (class "Default")
      (node (ref "IC3") (pin "1") (pinfunction "N.C._1") (pintype "bidirectional"))
    )
    (net (code "92") (name "unconnected-(IC4-TD-Pad4)") (class "Default")
      (node (ref "IC4") (pin "4") (pinfunction "TD_4") (pintype "bidirectional"))
    )
    (net (code "93") (name "unconnected-(IC5-ALERT{slash}RDY-Pad2)") (class "Default")
      (node (ref "IC5") (pin "2") (pinfunction "ALERT/RDY_2") (pintype "bidirectional"))
    )
    (net (code "94") (name "unconnected-(IC6-NC-Pad4)") (class "Default")
      (node (ref "IC6") (pin "4") (pinfunction "NC_4") (pintype "no_connect"))
    )
    (net (code "95") (name "unconnected-(Q1-D1{slash}D2_1-Pad2)") (class "Default")
      (node (ref "Q1") (pin "2") (pinfunction "D1/D2_1_2") (pintype "bidirectional"))
    )
    (net (code "96") (name "unconnected-(Q1-D1{slash}D2_2-Pad5)") (class "Default")
      (node (ref "Q1") (pin "5") (pinfunction "D1/D2_2_5") (pintype "bidirectional"))
    )
    (net (code "97") (name "unconnected-(R2-Pad1)") (class "Default")
      (node (ref "R2") (pin "1") (pinfunction "1_1") (pintype "passive"))
    )
    (net (code "98") (name "unconnected-(U$1-C7-PadP$9)") (class "Default")
      (node (ref "U$1") (pin "P$9") (pinfunction "C7_P$9") (pintype "bidirectional"))
    )
    (net (code "99") (name "unconnected-(U$1-R10-Pad15)") (class "Default")
      (node (ref "U$1") (pin "15") (pinfunction "R10_15") (pintype "bidirectional"))
    )
    (net (code "100") (name "unconnected-(U$1-R11-PadP$14)") (class "Default")
      (node (ref "U$1") (pin "P$14") (pinfunction "R11_P$14") (pintype "bidirectional"))
    )
    (net (code "101") (name "unconnected-(U$1-R12-PadP$13)") (class "Default")
      (node (ref "U$1") (pin "P$13") (pinfunction "R12_P$13") (pintype "bidirectional"))
    )
    (net (code "102") (name "unconnected-(U$1-R14-PadP$11)") (class "Default")
      (node (ref "U$1") (pin "P$11") (pinfunction "R14_P$11") (pintype "bidirectional"))
    )
    (net (code "103") (name "unconnected-(U$1-R15-PadP$10)") (class "Default")
      (node (ref "U$1") (pin "P$10") (pinfunction "R15_P$10") (pintype "bidirectional"))
    )
    (net (code "104") (name "unconnected-(U$5-FSPICS0-LO_SCK-G10-Pad14)") (class "Default")
      (node (ref "U$5") (pin "14") (pinfunction "FSPICS0-LO_SCK-G10_14") (pintype "bidirectional"))
    )
    (net (code "105") (name "unconnected-(U$5-G3-A1.3-LORA_DIO1-Pad7)") (class "Default")
      (node (ref "U$5") (pin "7") (pinfunction "G3-A1.3-LORA_DIO1_7") (pintype "bidirectional"))
    )
    (net (code "106") (name "unconnected-(U$5-G4-A1.4-LO_BY-MTMS-FSPIHD-Pad6)") (class "Default")
      (node (ref "U$5") (pin "6") (pinfunction "G4-A1.4-LO_BY-MTMS-FSPIHD_6") (pintype "bidirectional"))
    )
    (net (code "107") (name "unconnected-(U$5-G5-A2.0-LO_RST-MTDI-FSPIWP-Pad5)") (class "Default")
      (node (ref "U$5") (pin "5") (pinfunction "G5-A2.0-LO_RST-MTDI-FSPIWP_5") (pintype "bidirectional"))
    )
    (net (code "108") (name "unconnected-(U$5-G6-LO_MI-MTCK-FSPICK-Pad4)") (class "Default")
      (node (ref "U$5") (pin "4") (pinfunction "G6-LO_MI-MTCK-FSPICK_4") (pintype "bidirectional"))
    )
    (net (code "109") (name "unconnected-(U$5-G7-LO_MO-MTDO-FSPID-Pad3)") (class "Default")
      (node (ref "U$5") (pin "3") (pinfunction "G7-LO_MO-MTDO-FSPID_3") (pintype "bidirectional"))
    )
    (net (code "110") (name "unconnected-(U$5-LO_NSS-G8-Pad16)") (class "Default")
      (node (ref "U$5") (pin "16") (pinfunction "LO_NSS-G8_16") (pintype "bidirectional"))
    )
    (net (code "111") (name "unconnected-(U$6-PadM1)") (class "Default")
      (node (ref "U$6") (pin "M1") (pinfunction "M1_M1") (pintype "bidirectional"))
    )
    (net (code "112") (name "unconnected-(U$11-PadM2)") (class "Default")
      (node (ref "U$11") (pin "M2") (pinfunction "M2_M2") (pintype "bidirectional"))
    )
  )
)
